# ECU_Sheet4.net
KiCad netlist of a schematic drawn in Altium Designer
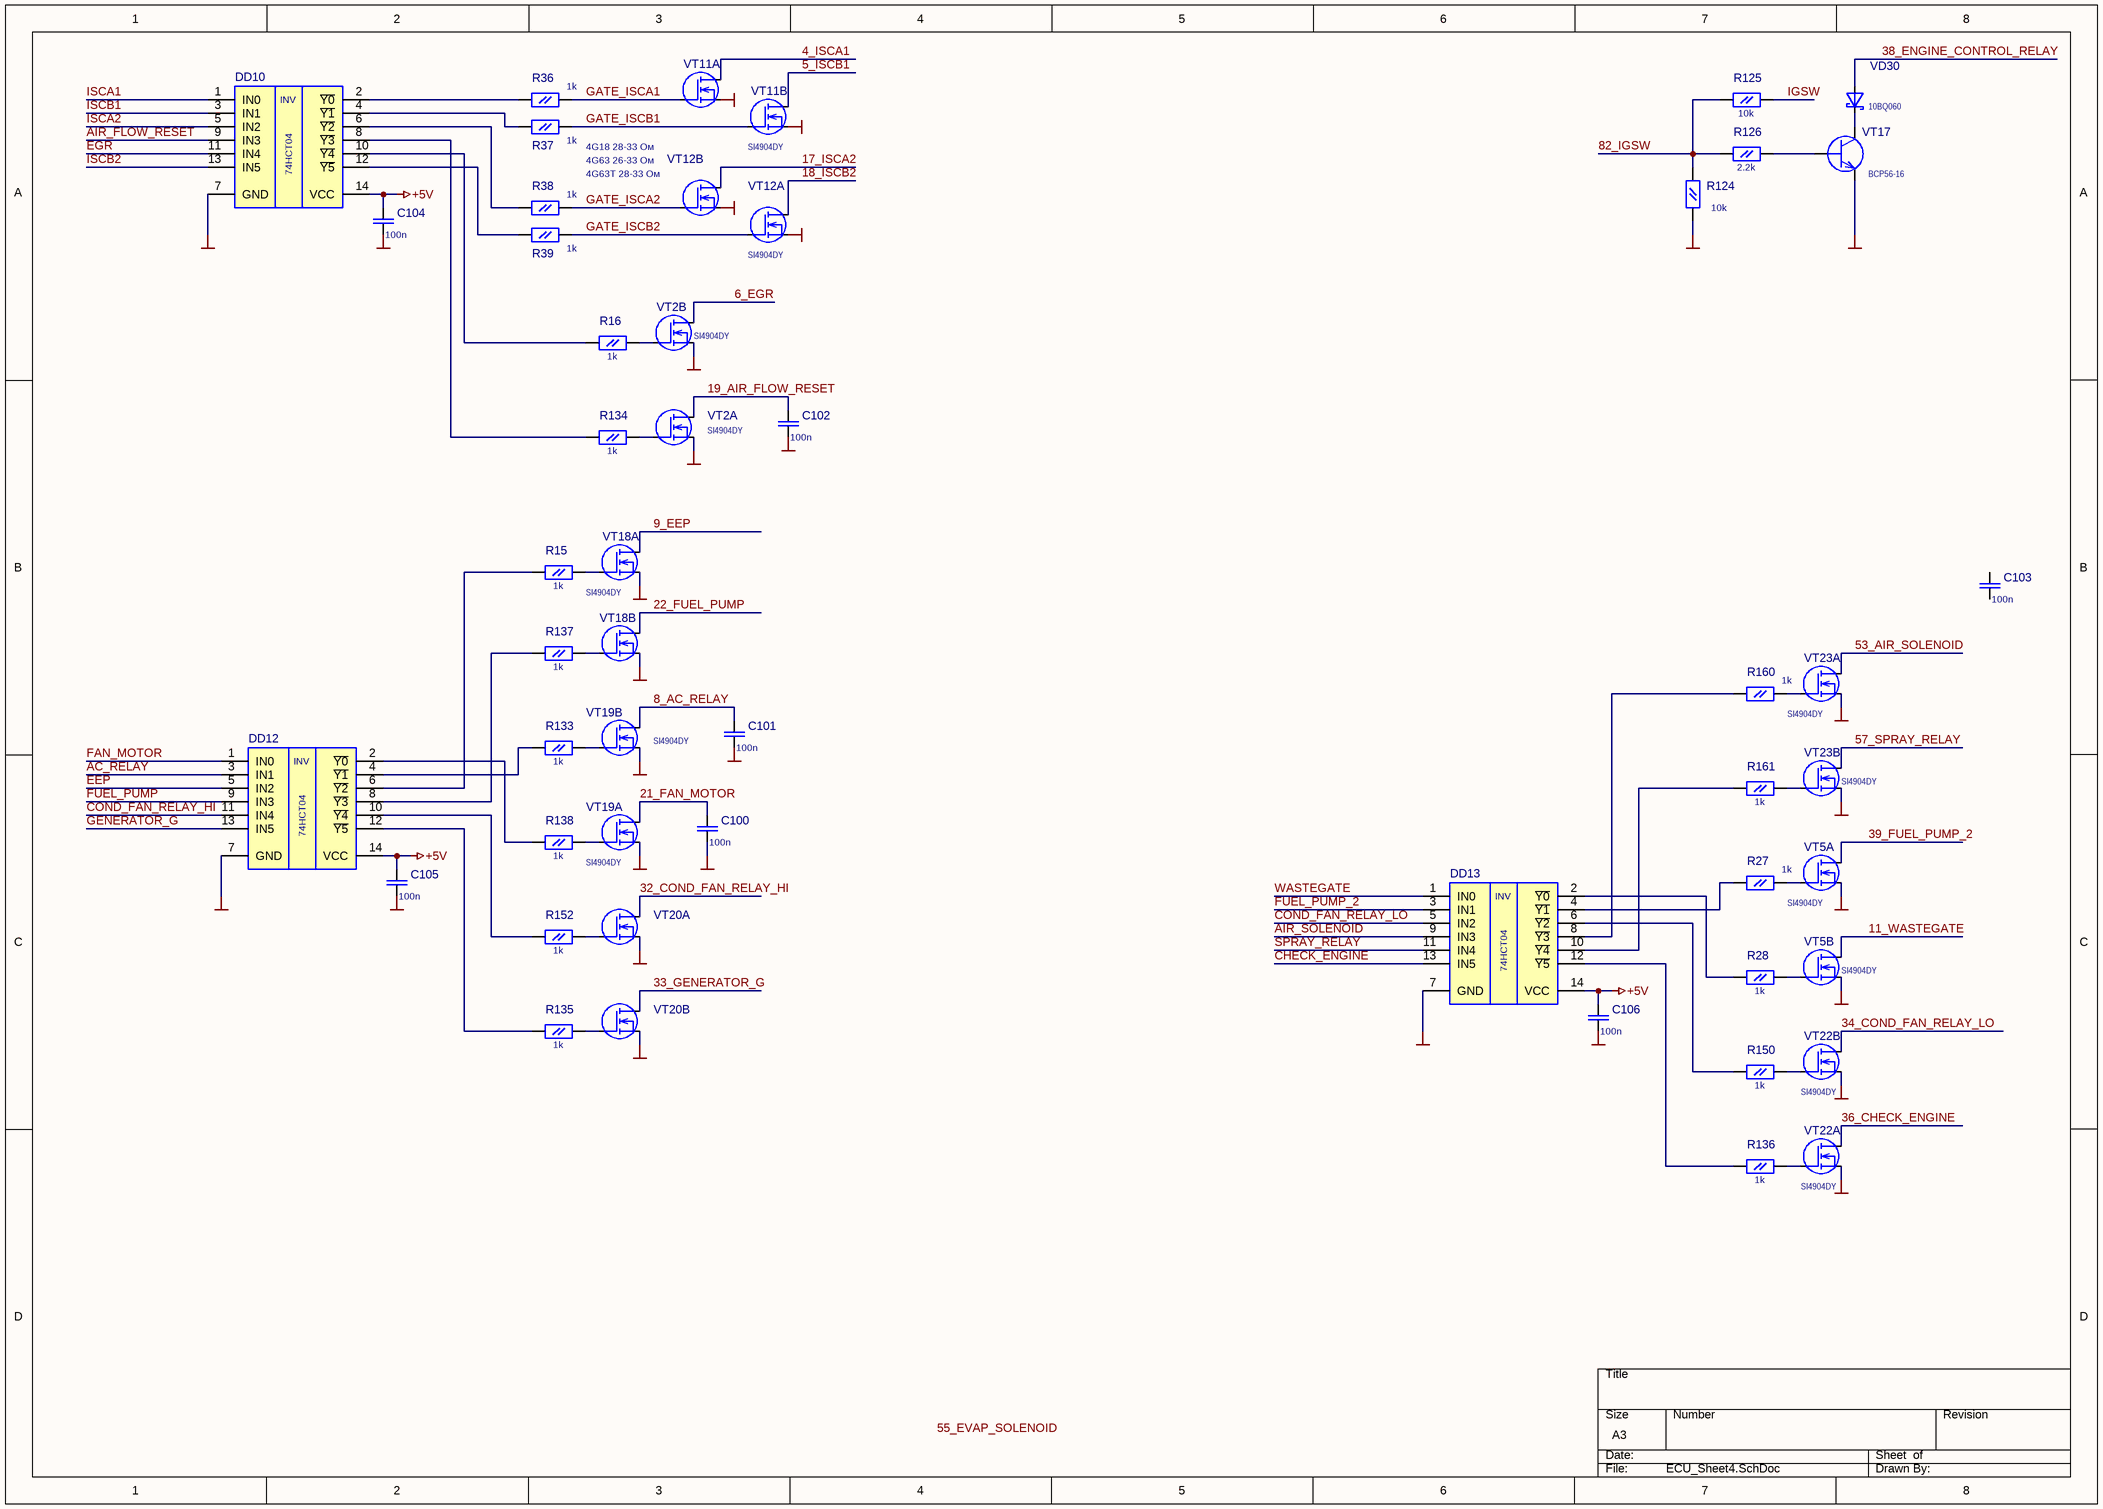
[diagram p0: ECU_Sheet4.SchDoc]

(export (version "E")
  (design (tool "Eeschema 10.0.6"))
  (components
    (comp (ref "C100")
      (value "100n")
      (footprint "C0805L")
      (description "C0603")
      (fields (field (name "Comment") "CSMD"))
      (libsource (lib "L1") (part "CSMD"))
    )
    (comp (ref "C101")
      (value "100n")
      (footprint "C0805L")
      (description "C0603")
      (fields (field (name "Comment") "CSMD"))
      (libsource (lib "L1") (part "CSMD"))
    )
    (comp (ref "C102")
      (value "100n")
      (footprint "C0805L")
      (description "C0603")
      (fields (field (name "Comment") "CSMD"))
      (libsource (lib "L1") (part "CSMD"))
    )
    (comp (ref "C103")
      (value "100n")
      (footprint "C0805L")
      (description "C0603")
      (fields (field (name "Comment") "CSMD"))
      (libsource (lib "L1") (part "CSMD"))
    )
    (comp (ref "C104")
      (value "100n")
      (footprint "C0805L")
      (description "C0603")
      (fields (field (name "Comment") "0.1мкФ-25В-X8R-10%"))
      (libsource (lib "L1") (part "CSMD"))
    )
    (comp (ref "C105")
      (value "100n")
      (footprint "C0805L")
      (description "C0603")
      (fields (field (name "Comment") "0.1мкФ-25В-X8R-10%"))
      (libsource (lib "L1") (part "CSMD"))
    )
    (comp (ref "C106")
      (value "100n")
      (footprint "C0805L")
      (description "C0603")
      (fields (field (name "Comment") "0.1мкФ-25В-X8R-10%"))
      (libsource (lib "L1") (part "CSMD"))
    )
    (comp (ref "DD10")
      (value "74HCT04")
      (footprint "TSSOP14 (JEDEC MO-153)")
      (libsource (lib "L1") (part "74HCT04"))
    )
    (comp (ref "DD12")
      (value "74HCT04")
      (footprint "TSSOP14 (JEDEC MO-153)")
      (libsource (lib "L1") (part "74HCT04"))
    )
    (comp (ref "DD13")
      (value "74HCT04")
      (footprint "TSSOP14 (JEDEC MO-153)")
      (libsource (lib "L1") (part "74HCT04"))
    )
    (comp (ref "R15")
      (value "1k")
      (footprint "R0805L")
      (description "R0805")
      (fields (field (name "Comment") "RSMD"))
      (libsource (lib "L1") (part "RSMD"))
    )
    (comp (ref "R16")
      (value "1k")
      (footprint "R0805L")
      (description "R0805")
      (fields (field (name "Comment") "RSMD"))
      (libsource (lib "L1") (part "RSMD"))
    )
    (comp (ref "R27")
      (value "1k")
      (footprint "R0805L")
      (description "R0805")
      (fields (field (name "Comment") "RSMD"))
      (libsource (lib "L1") (part "RSMD"))
    )
    (comp (ref "R28")
      (value "1k")
      (footprint "R0805L")
      (description "R0805")
      (fields (field (name "Comment") "RSMD"))
      (libsource (lib "L1") (part "RSMD"))
    )
    (comp (ref "R36")
      (value "1k")
      (footprint "R0805L")
      (description "R0805")
      (fields (field (name "Comment") "RSMD"))
      (libsource (lib "L1") (part "RSMD"))
    )
    (comp (ref "R37")
      (value "1k")
      (footprint "R0805L")
      (description "R0805")
      (fields (field (name "Comment") "RSMD"))
      (libsource (lib "L1") (part "RSMD"))
    )
    (comp (ref "R38")
      (value "1k")
      (footprint "R0805L")
      (description "R0805")
      (fields (field (name "Comment") "RSMD"))
      (libsource (lib "L1") (part "RSMD"))
    )
    (comp (ref "R39")
      (value "1k")
      (footprint "R0805L")
      (description "R0805")
      (fields (field (name "Comment") "RSMD"))
      (libsource (lib "L1") (part "RSMD"))
    )
    (comp (ref "R124")
      (value "10k")
      (footprint "R0805L")
      (description "R0805")
      (fields (field (name "Comment") "RSMD"))
      (libsource (lib "L1") (part "RSMD"))
    )
    (comp (ref "R125")
      (value "10k")
      (footprint "R0805L")
      (description "R0805")
      (fields (field (name "Comment") "RSMD"))
      (libsource (lib "L1") (part "RSMD"))
    )
    (comp (ref "R126")
      (value "2.2k")
      (footprint "R0805L")
      (description "R0805")
      (fields (field (name "Comment") "RSMD"))
      (libsource (lib "L1") (part "RSMD"))
    )
    (comp (ref "R133")
      (value "1k")
      (footprint "R0805L")
      (description "R0805")
      (fields (field (name "Comment") "RSMD"))
      (libsource (lib "L1") (part "RSMD"))
    )
    (comp (ref "R134")
      (value "1k")
      (footprint "R0805L")
      (description "R0805")
      (fields (field (name "Comment") "RSMD"))
      (libsource (lib "L1") (part "RSMD"))
    )
    (comp (ref "R135")
      (value "1k")
      (footprint "R0805L")
      (description "R0805")
      (fields (field (name "Comment") "RSMD"))
      (libsource (lib "L1") (part "RSMD"))
    )
    (comp (ref "R136")
      (value "1k")
      (footprint "R0805L")
      (description "R0805")
      (fields (field (name "Comment") "RSMD"))
      (libsource (lib "L1") (part "RSMD"))
    )
    (comp (ref "R137")
      (value "1k")
      (footprint "R0805L")
      (description "R0805")
      (fields (field (name "Comment") "RSMD"))
      (libsource (lib "L1") (part "RSMD"))
    )
    (comp (ref "R138")
      (value "1k")
      (footprint "R0805L")
      (description "R0805")
      (fields (field (name "Comment") "RSMD"))
      (libsource (lib "L1") (part "RSMD"))
    )
    (comp (ref "R150")
      (value "1k")
      (footprint "R0805L")
      (description "R0805")
      (fields (field (name "Comment") "RSMD"))
      (libsource (lib "L1") (part "RSMD"))
    )
    (comp (ref "R152")
      (value "1k")
      (footprint "R0805L")
      (description "R0805")
      (fields (field (name "Comment") "RSMD"))
      (libsource (lib "L1") (part "RSMD"))
    )
    (comp (ref "R160")
      (value "1k")
      (footprint "R0805L")
      (description "R0805")
      (fields (field (name "Comment") "RSMD"))
      (libsource (lib "L1") (part "RSMD"))
    )
    (comp (ref "R161")
      (value "1k")
      (footprint "R0805L")
      (description "R0805")
      (fields (field (name "Comment") "RSMD"))
      (libsource (lib "L1") (part "RSMD"))
    )
    (comp (ref "VD30")
      (value "10BQ060")
      (footprint "RL1:DO-214AA SMB")
      (libsource (lib "RL1") (part "10BQ060"))
    )
    (comp (ref "VT2")
      (value "SI4904DY")
      (footprint "SOIC8 DBL FET")
      (description "SI4904DY или IRF7341TRPBF или SI4908DY")
      (libsource (lib "L1") (part "SQ9945BEY"))
    )
    (comp (ref "VT5")
      (value "SI4904DY")
      (footprint "SOIC8 DBL FET")
      (description "SI4904DY или IRF7341TRPBF или SI4908DY")
      (libsource (lib "L1") (part "SQ9945BEY"))
    )
    (comp (ref "VT11")
      (value "SI4904DY")
      (footprint "SOIC8 DBL FET")
      (description "SI4904DY или IRF7341TRPBF или SI4908DY")
      (libsource (lib "L1") (part "SQ9945BEY"))
    )
    (comp (ref "VT12")
      (value "SI4904DY")
      (footprint "SOIC8 DBL FET")
      (description "SI4904DY или IRF7341TRPBF или SI4908DY")
      (libsource (lib "L1") (part "SQ9945BEY"))
    )
    (comp (ref "VT17") (value "BCP56-16") (footprint "SOT-223 PWR") (libsource (lib "L1") (part "BCP56-16")))
    (comp (ref "VT18")
      (value "SI4904DY")
      (footprint "SOIC8 DBL FET")
      (description "SI4904DY или IRF7341TRPBF или SI4908DY")
      (libsource (lib "L1") (part "SQ9945BEY"))
    )
    (comp (ref "VT19")
      (value "SI4904DY")
      (footprint "SOIC8 DBL FET")
      (description "SI4904DY или IRF7341TRPBF или SI4908DY")
      (libsource (lib "L1") (part "SQ9945BEY"))
    )
    (comp (ref "VT20")
      (value "SI4904DY")
      (footprint "SOIC8 DBL FET")
      (description "SI4904DY или IRF7341TRPBF или SI4908DY")
      (libsource (lib "L1") (part "SQ9945BEY"))
    )
    (comp (ref "VT22")
      (value "SI4904DY")
      (footprint "SOIC8 DBL FET")
      (description "SI4904DY или IRF7341TRPBF или SI4908DY")
      (libsource (lib "L1") (part "SQ9945BEY"))
    )
    (comp (ref "VT23")
      (value "SI4904DY")
      (footprint "SOIC8 DBL FET")
      (description "SI4904DY или IRF7341TRPBF или SI4908DY")
      (libsource (lib "L1") (part "SQ9945BEY"))
    )
  )
  (nets
    (net (code "1") (name "+5V") (class "Default")
      (node (ref "C104") (pin "1") (pintype "passive"))
      (node (ref "C105") (pin "1") (pintype "passive"))
      (node (ref "C106") (pin "1") (pintype "passive"))
      (node (ref "DD10") (pin "14") (pinfunction "VCC_14") (pintype "passive"))
      (node (ref "DD12") (pin "14") (pinfunction "VCC_14") (pintype "passive"))
      (node (ref "DD13") (pin "14") (pinfunction "VCC_14") (pintype "passive"))
    )
    (net (code "2") (name "/4_ISCA1") (class "Default") (node (ref "VT11") (pin "6") (pintype "passive")))
    (net (code "3") (name "/5_ISCB1") (class "Default") (node (ref "VT11") (pin "5") (pintype "passive")))
    (net (code "4") (name "/6_EGR") (class "Default") (node (ref "VT2") (pin "5") (pintype "passive")))
    (net (code "5") (name "/8_AC_RELAY") (class "Default")
      (node (ref "C101") (pin "1") (pintype "passive"))
      (node (ref "VT19") (pin "5") (pintype "passive"))
    )
    (net (code "6") (name "/9_EEP") (class "Default") (node (ref "VT18") (pin "6") (pintype "passive")))
    (net (code "7") (name "/11_WASTEGATE") (class "Default") (node (ref "VT5") (pin "5") (pintype "passive")))
    (net (code "8") (name "/17_ISCA2") (class "Default") (node (ref "VT12") (pin "5") (pintype "passive")))
    (net (code "9") (name "/18_ISCB2") (class "Default") (node (ref "VT12") (pin "6") (pintype "passive")))
    (net (code "10") (name "/19_AIR_FLOW_RESET") (class "Default")
      (node (ref "C102") (pin "1") (pintype "passive"))
      (node (ref "VT2") (pin "6") (pintype "passive"))
    )
    (net (code "11") (name "/21_FAN_MOTOR") (class "Default")
      (node (ref "C100") (pin "1") (pintype "passive"))
      (node (ref "VT19") (pin "6") (pintype "passive"))
    )
    (net (code "12") (name "/22_FUEL_PUMP") (class "Default")
      (node (ref "VT18") (pin "5") (pintype "passive"))
    )
    (net (code "13") (name "/32_COND_FAN_RELAY_HI") (class "Default")
      (node (ref "VT20") (pin "6") (pintype "passive"))
    )
    (net (code "14") (name "/33_GENERATOR_G") (class "Default")
      (node (ref "VT20") (pin "5") (pintype "passive"))
    )
    (net (code "15") (name "/34_COND_FAN_RELAY_LO") (class "Default")
      (node (ref "VT22") (pin "5") (pintype "passive"))
    )
    (net (code "16") (name "/36_CHECK_ENGINE") (class "Default")
      (node (ref "VT22") (pin "6") (pintype "passive"))
    )
    (net (code "17") (name "/38_ENGINE_CONTROL_RELAY") (class "Default")
      (node (ref "VD30") (pin "1") (pintype "passive"))
    )
    (net (code "18") (name "/39_FUEL_PUMP_2") (class "Default")
      (node (ref "VT5") (pin "6") (pintype "passive"))
    )
    (net (code "19") (name "/53_AIR_SOLENOID") (class "Default")
      (node (ref "VT23") (pin "6") (pintype "passive"))
    )
    (net (code "21") (name "/57_SPRAY_RELAY") (class "Default")
      (node (ref "VT23") (pin "5") (pintype "passive"))
    )
    (net (code "22") (name "/82_IGSW") (class "Default")
      (node (ref "R124") (pin "2") (pinfunction "Pin2_2") (pintype "passive"))
      (node (ref "R125") (pin "1") (pinfunction "Pin1_1") (pintype "passive"))
      (node (ref "R126") (pin "1") (pinfunction "Pin1_1") (pintype "passive"))
    )
    (net (code "23") (name "/AC_RELAY") (class "Default")
      (node (ref "DD12") (pin "3") (pinfunction "IN1_3") (pintype "passive"))
    )
    (net (code "24") (name "/AIR_FLOW_RESET") (class "Default")
      (node (ref "DD10") (pin "9") (pinfunction "IN3_9") (pintype "passive"))
    )
    (net (code "25") (name "/AIR_SOLENOID") (class "Default")
      (node (ref "DD13") (pin "9") (pinfunction "IN3_9") (pintype "passive"))
    )
    (net (code "26") (name "/CHECK_ENGINE") (class "Default")
      (node (ref "DD13") (pin "13") (pinfunction "IN5_13") (pintype "passive"))
    )
    (net (code "27") (name "/COND_FAN_RELAY_HI") (class "Default")
      (node (ref "DD12") (pin "11") (pinfunction "IN4_11") (pintype "passive"))
    )
    (net (code "28") (name "/COND_FAN_RELAY_LO") (class "Default")
      (node (ref "DD13") (pin "5") (pinfunction "IN2_5") (pintype "passive"))
    )
    (net (code "29") (name "/EEP") (class "Default")
      (node (ref "DD12") (pin "5") (pinfunction "IN2_5") (pintype "passive"))
    )
    (net (code "30") (name "/EGR") (class "Default")
      (node (ref "DD10") (pin "11") (pinfunction "IN4_11") (pintype "passive"))
    )
    (net (code "31") (name "/FAN_MOTOR") (class "Default")
      (node (ref "DD12") (pin "1") (pinfunction "IN0_1") (pintype "passive"))
    )
    (net (code "32") (name "/FUEL_PUMP") (class "Default")
      (node (ref "DD12") (pin "9") (pinfunction "IN3_9") (pintype "passive"))
    )
    (net (code "33") (name "/FUEL_PUMP_2") (class "Default")
      (node (ref "DD13") (pin "3") (pinfunction "IN1_3") (pintype "passive"))
    )
    (net (code "34") (name "/GATE_ISCA1") (class "Default")
      (node (ref "R36") (pin "2") (pinfunction "Pin2_2") (pintype "passive"))
      (node (ref "VT11") (pin "2") (pintype "passive"))
    )
    (net (code "35") (name "/GATE_ISCA2") (class "Default")
      (node (ref "R38") (pin "2") (pinfunction "Pin2_2") (pintype "passive"))
      (node (ref "VT12") (pin "4") (pintype "passive"))
    )
    (net (code "36") (name "/GATE_ISCB1") (class "Default")
      (node (ref "R37") (pin "2") (pinfunction "Pin2_2") (pintype "passive"))
      (node (ref "VT11") (pin "4") (pintype "passive"))
    )
    (net (code "37") (name "/GATE_ISCB2") (class "Default")
      (node (ref "R39") (pin "2") (pinfunction "Pin2_2") (pintype "passive"))
      (node (ref "VT12") (pin "2") (pintype "passive"))
    )
    (net (code "38") (name "/GENERATOR_G") (class "Default")
      (node (ref "DD12") (pin "13") (pinfunction "IN5_13") (pintype "passive"))
    )
    (net (code "39") (name "/IGSW") (class "Default")
      (node (ref "R125") (pin "2") (pinfunction "Pin2_2") (pintype "passive"))
    )
    (net (code "40") (name "/ISCA1") (class "Default")
      (node (ref "DD10") (pin "1") (pinfunction "IN0_1") (pintype "passive"))
    )
    (net (code "41") (name "/ISCA2") (class "Default")
      (node (ref "DD10") (pin "5") (pinfunction "IN2_5") (pintype "passive"))
    )
    (net (code "42") (name "/ISCB1") (class "Default")
      (node (ref "DD10") (pin "3") (pinfunction "IN1_3") (pintype "passive"))
    )
    (net (code "43") (name "/ISCB2") (class "Default")
      (node (ref "DD10") (pin "13") (pinfunction "IN5_13") (pintype "passive"))
    )
    (net (code "44") (name "/SPRAY_RELAY") (class "Default")
      (node (ref "DD13") (pin "11") (pinfunction "IN4_11") (pintype "passive"))
    )
    (net (code "45") (name "/WASTEGATE") (class "Default")
      (node (ref "DD13") (pin "1") (pinfunction "IN0_1") (pintype "passive"))
    )
    (net (code "46") (name "GND") (class "Default")
      (node (ref "C100") (pin "2") (pintype "passive"))
      (node (ref "C101") (pin "2") (pintype "passive"))
      (node (ref "C102") (pin "2") (pintype "passive"))
      (node (ref "C104") (pin "2") (pintype "passive"))
      (node (ref "C105") (pin "2") (pintype "passive"))
      (node (ref "C106") (pin "2") (pintype "passive"))
      (node (ref "DD10") (pin "7") (pinfunction "GND_7") (pintype "passive"))
      (node (ref "DD12") (pin "7") (pinfunction "GND_7") (pintype "passive"))
      (node (ref "DD13") (pin "7") (pinfunction "GND_7") (pintype "passive"))
      (node (ref "R124") (pin "1") (pinfunction "Pin1_1") (pintype "passive"))
      (node (ref "VT11") (pin "1") (pintype "passive"))
      (node (ref "VT11") (pin "3") (pintype "passive"))
      (node (ref "VT12") (pin "1") (pintype "passive"))
      (node (ref "VT12") (pin "3") (pintype "passive"))
      (node (ref "VT17") (pin "3") (pinfunction "E_3") (pintype "passive"))
      (node (ref "VT18") (pin "1") (pintype "passive"))
      (node (ref "VT18") (pin "3") (pintype "passive"))
      (node (ref "VT19") (pin "1") (pintype "passive"))
      (node (ref "VT19") (pin "3") (pintype "passive"))
      (node (ref "VT2") (pin "1") (pintype "passive"))
      (node (ref "VT2") (pin "3") (pintype "passive"))
      (node (ref "VT20") (pin "1") (pintype "passive"))
      (node (ref "VT20") (pin "3") (pintype "passive"))
      (node (ref "VT22") (pin "1") (pintype "passive"))
      (node (ref "VT22") (pin "3") (pintype "passive"))
      (node (ref "VT23") (pin "1") (pintype "passive"))
      (node (ref "VT23") (pin "3") (pintype "passive"))
      (node (ref "VT5") (pin "1") (pintype "passive"))
      (node (ref "VT5") (pin "3") (pintype "passive"))
    )
    (net (code "47") (name "Net-(DD10-~{Y0})") (class "Default")
      (node (ref "DD10") (pin "2") (pinfunction "~{Y0}_2") (pintype "passive"))
      (node (ref "R36") (pin "1") (pinfunction "Pin1_1") (pintype "passive"))
    )
    (net (code "48") (name "Net-(DD10-~{Y1})") (class "Default")
      (node (ref "DD10") (pin "4") (pinfunction "~{Y1}_4") (pintype "passive"))
      (node (ref "R37") (pin "1") (pinfunction "Pin1_1") (pintype "passive"))
    )
    (net (code "49") (name "Net-(DD10-~{Y2})") (class "Default")
      (node (ref "DD10") (pin "6") (pinfunction "~{Y2}_6") (pintype "passive"))
      (node (ref "R38") (pin "1") (pinfunction "Pin1_1") (pintype "passive"))
    )
    (net (code "50") (name "Net-(DD10-~{Y3})") (class "Default")
      (node (ref "DD10") (pin "8") (pinfunction "~{Y3}_8") (pintype "passive"))
      (node (ref "R134") (pin "1") (pinfunction "Pin1_1") (pintype "passive"))
    )
    (net (code "51") (name "Net-(DD10-~{Y4})") (class "Default")
      (node (ref "DD10") (pin "10") (pinfunction "~{Y4}_10") (pintype "passive"))
      (node (ref "R16") (pin "1") (pinfunction "Pin1_1") (pintype "passive"))
    )
    (net (code "52") (name "Net-(DD10-~{Y5})") (class "Default")
      (node (ref "DD10") (pin "12") (pinfunction "~{Y5}_12") (pintype "passive"))
      (node (ref "R39") (pin "1") (pinfunction "Pin1_1") (pintype "passive"))
    )
    (net (code "53") (name "Net-(DD12-~{Y0})") (class "Default")
      (node (ref "DD12") (pin "2") (pinfunction "~{Y0}_2") (pintype "passive"))
      (node (ref "R138") (pin "1") (pinfunction "Pin1_1") (pintype "passive"))
    )
    (net (code "54") (name "Net-(DD12-~{Y1})") (class "Default")
      (node (ref "DD12") (pin "4") (pinfunction "~{Y1}_4") (pintype "passive"))
      (node (ref "R133") (pin "1") (pinfunction "Pin1_1") (pintype "passive"))
    )
    (net (code "55") (name "Net-(DD12-~{Y2})") (class "Default")
      (node (ref "DD12") (pin "6") (pinfunction "~{Y2}_6") (pintype "passive"))
      (node (ref "R15") (pin "1") (pinfunction "Pin1_1") (pintype "passive"))
    )
    (net (code "56") (name "Net-(DD12-~{Y3})") (class "Default")
      (node (ref "DD12") (pin "8") (pinfunction "~{Y3}_8") (pintype "passive"))
      (node (ref "R137") (pin "1") (pinfunction "Pin1_1") (pintype "passive"))
    )
    (net (code "57") (name "Net-(DD12-~{Y4})") (class "Default")
      (node (ref "DD12") (pin "10") (pinfunction "~{Y4}_10") (pintype "passive"))
      (node (ref "R152") (pin "1") (pinfunction "Pin1_1") (pintype "passive"))
    )
    (net (code "58") (name "Net-(DD12-~{Y5})") (class "Default")
      (node (ref "DD12") (pin "12") (pinfunction "~{Y5}_12") (pintype "passive"))
      (node (ref "R135") (pin "1") (pinfunction "Pin1_1") (pintype "passive"))
    )
    (net (code "59") (name "Net-(DD13-~{Y0})") (class "Default")
      (node (ref "DD13") (pin "2") (pinfunction "~{Y0}_2") (pintype "passive"))
      (node (ref "R28") (pin "1") (pinfunction "Pin1_1") (pintype "passive"))
    )
    (net (code "60") (name "Net-(DD13-~{Y1})") (class "Default")
      (node (ref "DD13") (pin "4") (pinfunction "~{Y1}_4") (pintype "passive"))
      (node (ref "R27") (pin "1") (pinfunction "Pin1_1") (pintype "passive"))
    )
    (net (code "61") (name "Net-(DD13-~{Y2})") (class "Default")
      (node (ref "DD13") (pin "6") (pinfunction "~{Y2}_6") (pintype "passive"))
      (node (ref "R150") (pin "1") (pinfunction "Pin1_1") (pintype "passive"))
    )
    (net (code "62") (name "Net-(DD13-~{Y3})") (class "Default")
      (node (ref "DD13") (pin "8") (pinfunction "~{Y3}_8") (pintype "passive"))
      (node (ref "R160") (pin "1") (pinfunction "Pin1_1") (pintype "passive"))
    )
    (net (code "63") (name "Net-(DD13-~{Y4})") (class "Default")
      (node (ref "DD13") (pin "10") (pinfunction "~{Y4}_10") (pintype "passive"))
      (node (ref "R161") (pin "1") (pinfunction "Pin1_1") (pintype "passive"))
    )
    (net (code "64") (name "Net-(DD13-~{Y5})") (class "Default")
      (node (ref "DD13") (pin "12") (pinfunction "~{Y5}_12") (pintype "passive"))
      (node (ref "R136") (pin "1") (pinfunction "Pin1_1") (pintype "passive"))
    )
    (net (code "65") (name "Net-(R15-Pin2)") (class "Default")
      (node (ref "R15") (pin "2") (pinfunction "Pin2_2") (pintype "passive"))
      (node (ref "VT18") (pin "2") (pintype "passive"))
    )
    (net (code "66") (name "Net-(R16-Pin2)") (class "Default")
      (node (ref "R16") (pin "2") (pinfunction "Pin2_2") (pintype "passive"))
      (node (ref "VT2") (pin "4") (pintype "passive"))
    )
    (net (code "67") (name "Net-(R27-Pin2)") (class "Default")
      (node (ref "R27") (pin "2") (pinfunction "Pin2_2") (pintype "passive"))
      (node (ref "VT5") (pin "2") (pintype "passive"))
    )
    (net (code "68") (name "Net-(R28-Pin2)") (class "Default")
      (node (ref "R28") (pin "2") (pinfunction "Pin2_2") (pintype "passive"))
      (node (ref "VT5") (pin "4") (pintype "passive"))
    )
    (net (code "69") (name "Net-(R126-Pin2)") (class "Default")
      (node (ref "R126") (pin "2") (pinfunction "Pin2_2") (pintype "passive"))
      (node (ref "VT17") (pin "1") (pinfunction "B_1") (pintype "passive"))
    )
    (net (code "70") (name "Net-(R133-Pin2)") (class "Default")
      (node (ref "R133") (pin "2") (pinfunction "Pin2_2") (pintype "passive"))
      (node (ref "VT19") (pin "4") (pintype "passive"))
    )
    (net (code "71") (name "Net-(R134-Pin2)") (class "Default")
      (node (ref "R134") (pin "2") (pinfunction "Pin2_2") (pintype "passive"))
      (node (ref "VT2") (pin "2") (pintype "passive"))
    )
    (net (code "72") (name "Net-(R135-Pin2)") (class "Default")
      (node (ref "R135") (pin "2") (pinfunction "Pin2_2") (pintype "passive"))
      (node (ref "VT20") (pin "4") (pintype "passive"))
    )
    (net (code "73") (name "Net-(R136-Pin2)") (class "Default")
      (node (ref "R136") (pin "2") (pinfunction "Pin2_2") (pintype "passive"))
      (node (ref "VT22") (pin "2") (pintype "passive"))
    )
    (net (code "74") (name "Net-(R137-Pin2)") (class "Default")
      (node (ref "R137") (pin "2") (pinfunction "Pin2_2") (pintype "passive"))
      (node (ref "VT18") (pin "4") (pintype "passive"))
    )
    (net (code "75") (name "Net-(R138-Pin2)") (class "Default")
      (node (ref "R138") (pin "2") (pinfunction "Pin2_2") (pintype "passive"))
      (node (ref "VT19") (pin "2") (pintype "passive"))
    )
    (net (code "76") (name "Net-(R150-Pin2)") (class "Default")
      (node (ref "R150") (pin "2") (pinfunction "Pin2_2") (pintype "passive"))
      (node (ref "VT22") (pin "4") (pintype "passive"))
    )
    (net (code "77") (name "Net-(R152-Pin2)") (class "Default")
      (node (ref "R152") (pin "2") (pinfunction "Pin2_2") (pintype "passive"))
      (node (ref "VT20") (pin "2") (pintype "passive"))
    )
    (net (code "78") (name "Net-(R160-Pin2)") (class "Default")
      (node (ref "R160") (pin "2") (pinfunction "Pin2_2") (pintype "passive"))
      (node (ref "VT23") (pin "2") (pintype "passive"))
    )
    (net (code "79") (name "Net-(R161-Pin2)") (class "Default")
      (node (ref "R161") (pin "2") (pinfunction "Pin2_2") (pintype "passive"))
      (node (ref "VT23") (pin "4") (pintype "passive"))
    )
    (net (code "80") (name "Net-(VT17-C)") (class "Default")
      (node (ref "VD30") (pin "2") (pintype "passive"))
      (node (ref "VT17") (pin "2") (pinfunction "C_2") (pintype "passive"))
    )
    (net (code "81") (name "unconnected-(C103-Pad1)") (class "Default")
      (node (ref "C103") (pin "1") (pintype "passive"))
    )
    (net (code "82") (name "unconnected-(C103-Pad2)") (class "Default")
      (node (ref "C103") (pin "2") (pintype "passive"))
    )
  )
)
